# BFA_sch.net
KiCad netlist of a schematic drawn in EAGLE
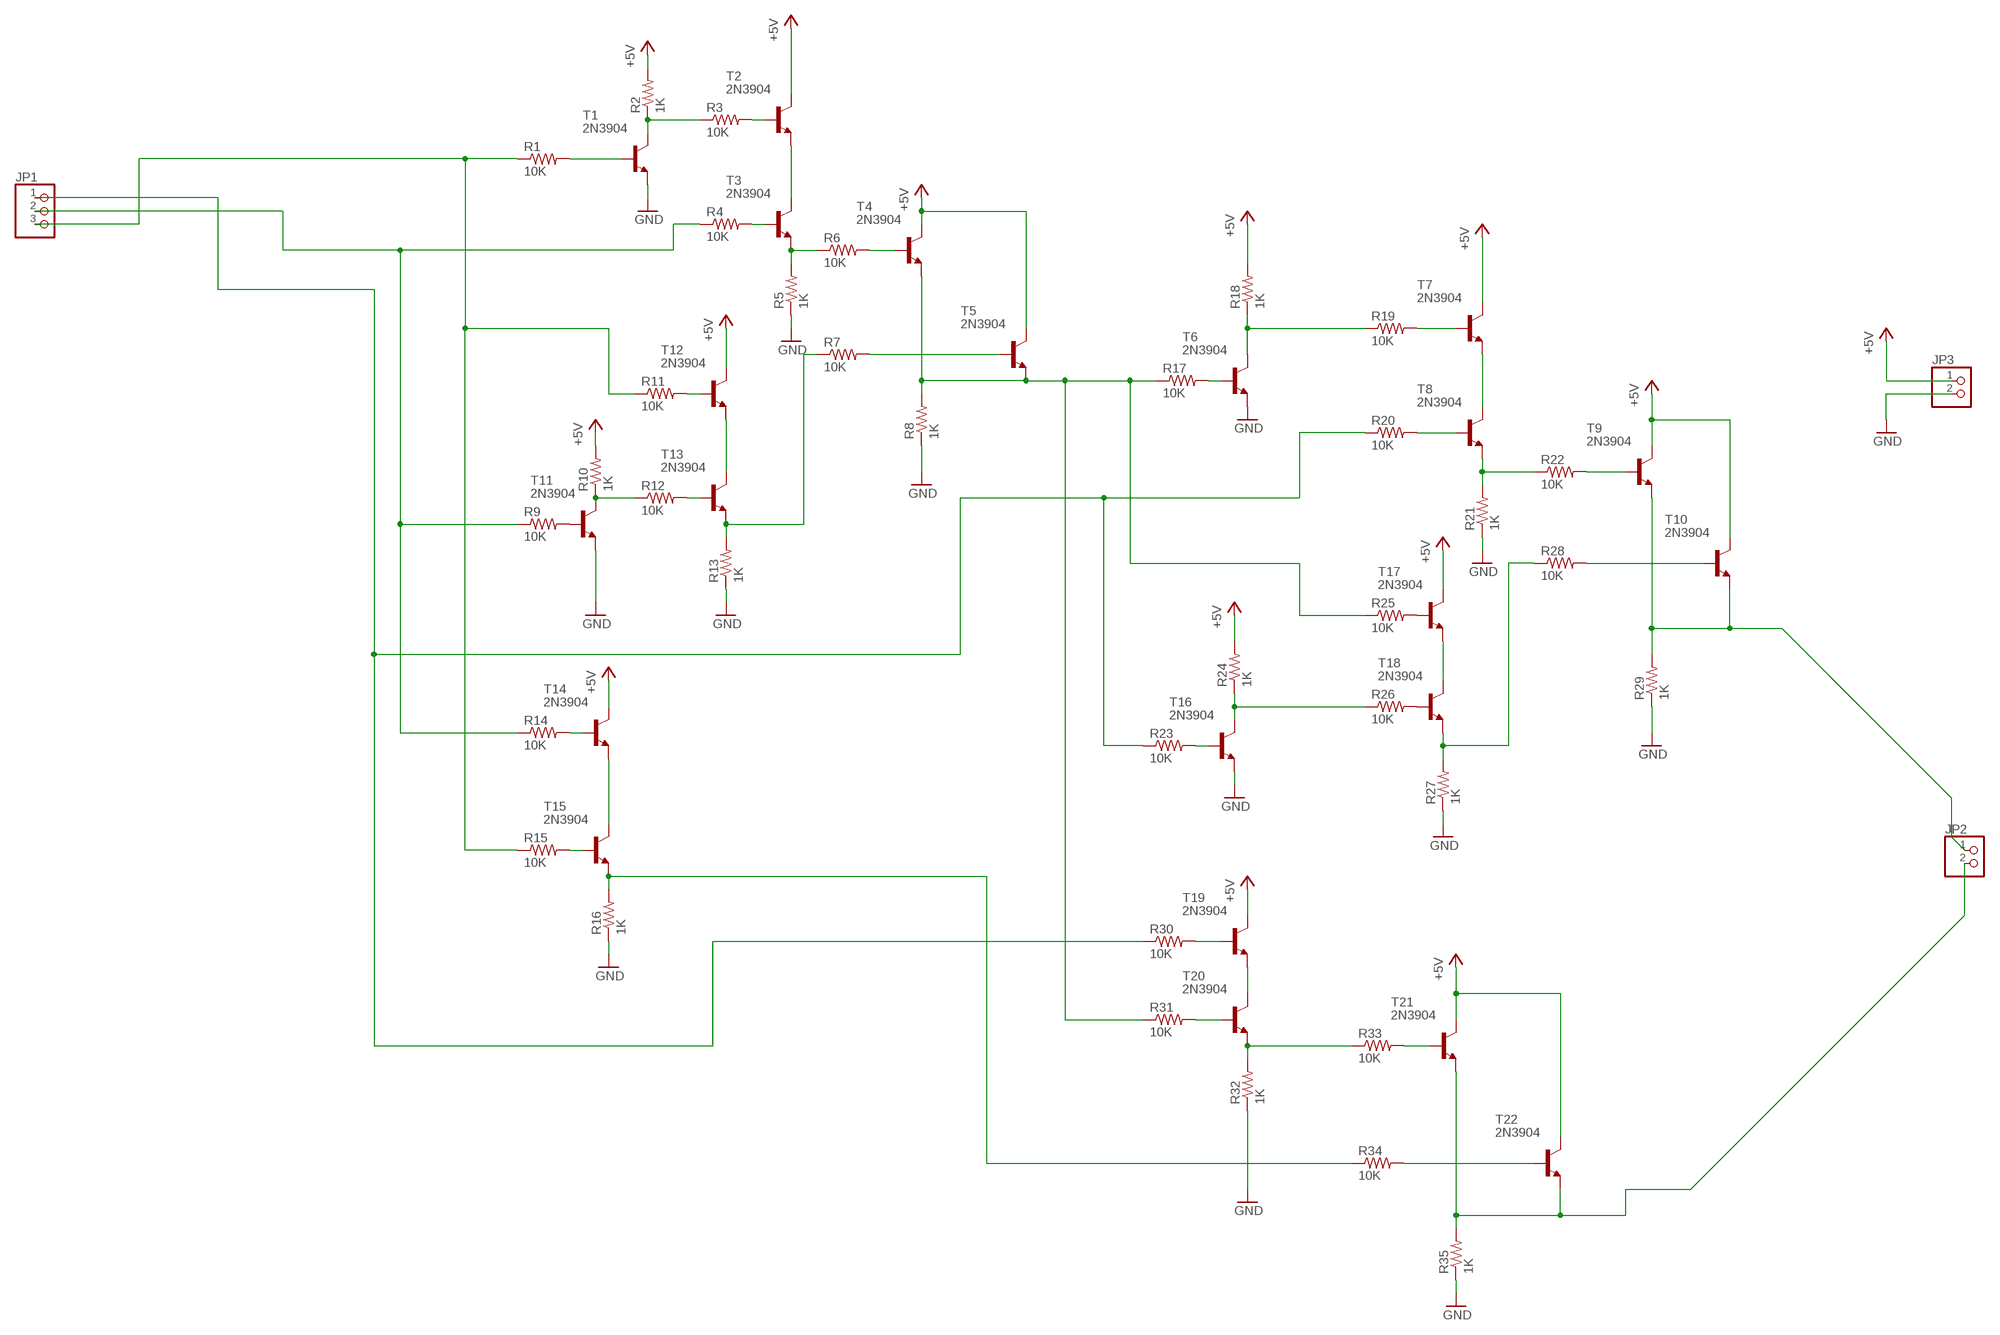
[diagram p0: schematic, sheet 1]

(export (version "E")
  (design (tool "Eeschema 10.0.6"))
  (components
    (comp (ref "JP1")
      (value "PINHD-1X3/90")
      (footprint "eagle-import:1X03_90")
      (libsource (lib "eagle-import") (part "PINHD-1X3/90"))
    )
    (comp (ref "JP2")
      (value "PINHD-1X2/90")
      (footprint "eagle-import:1X02_90")
      (libsource (lib "eagle-import") (part "PINHD-1X2/90"))
    )
    (comp (ref "JP3")
      (value "PINHD-1X2/90")
      (footprint "eagle-import:1X02_90")
      (libsource (lib "eagle-import") (part "PINHD-1X2/90"))
    )
    (comp (ref "R1")
      (value "10K")
      (footprint "eagle-import:0204_7")
      (libsource (lib "eagle-import") (part "R-US_0204/7"))
    )
    (comp (ref "R2")
      (value "1K")
      (footprint "eagle-import:0204_7")
      (libsource (lib "eagle-import") (part "R-US_0204/7"))
    )
    (comp (ref "R3")
      (value "10K")
      (footprint "eagle-import:0204_7")
      (libsource (lib "eagle-import") (part "R-US_0204/7"))
    )
    (comp (ref "R4")
      (value "10K")
      (footprint "eagle-import:0204_7")
      (libsource (lib "eagle-import") (part "R-US_0204/7"))
    )
    (comp (ref "R5")
      (value "1K")
      (footprint "eagle-import:0204_7")
      (libsource (lib "eagle-import") (part "R-US_0204/7"))
    )
    (comp (ref "R6")
      (value "10K")
      (footprint "eagle-import:0204_7")
      (libsource (lib "eagle-import") (part "R-US_0204/7"))
    )
    (comp (ref "R7")
      (value "10K")
      (footprint "eagle-import:0204_7")
      (libsource (lib "eagle-import") (part "R-US_0204/7"))
    )
    (comp (ref "R8")
      (value "1K")
      (footprint "eagle-import:0204_7")
      (libsource (lib "eagle-import") (part "R-US_0204/7"))
    )
    (comp (ref "R9")
      (value "10K")
      (footprint "eagle-import:0204_7")
      (libsource (lib "eagle-import") (part "R-US_0204/7"))
    )
    (comp (ref "R10")
      (value "1K")
      (footprint "eagle-import:0204_7")
      (libsource (lib "eagle-import") (part "R-US_0204/7"))
    )
    (comp (ref "R11")
      (value "10K")
      (footprint "eagle-import:0204_7")
      (libsource (lib "eagle-import") (part "R-US_0204/7"))
    )
    (comp (ref "R12")
      (value "10K")
      (footprint "eagle-import:0204_7")
      (libsource (lib "eagle-import") (part "R-US_0204/7"))
    )
    (comp (ref "R13")
      (value "1K")
      (footprint "eagle-import:0204_7")
      (libsource (lib "eagle-import") (part "R-US_0204/7"))
    )
    (comp (ref "R14")
      (value "10K")
      (footprint "eagle-import:0204_7")
      (libsource (lib "eagle-import") (part "R-US_0204/7"))
    )
    (comp (ref "R15")
      (value "10K")
      (footprint "eagle-import:0204_7")
      (libsource (lib "eagle-import") (part "R-US_0204/7"))
    )
    (comp (ref "R16")
      (value "1K")
      (footprint "eagle-import:0204_7")
      (libsource (lib "eagle-import") (part "R-US_0204/7"))
    )
    (comp (ref "R17")
      (value "10K")
      (footprint "eagle-import:0204_7")
      (libsource (lib "eagle-import") (part "R-US_0204/7"))
    )
    (comp (ref "R18")
      (value "1K")
      (footprint "eagle-import:0204_7")
      (libsource (lib "eagle-import") (part "R-US_0204/7"))
    )
    (comp (ref "R19")
      (value "10K")
      (footprint "eagle-import:0204_7")
      (libsource (lib "eagle-import") (part "R-US_0204/7"))
    )
    (comp (ref "R20")
      (value "10K")
      (footprint "eagle-import:0204_7")
      (libsource (lib "eagle-import") (part "R-US_0204/7"))
    )
    (comp (ref "R21")
      (value "1K")
      (footprint "eagle-import:0204_7")
      (libsource (lib "eagle-import") (part "R-US_0204/7"))
    )
    (comp (ref "R22")
      (value "10K")
      (footprint "eagle-import:0204_7")
      (libsource (lib "eagle-import") (part "R-US_0204/7"))
    )
    (comp (ref "R23")
      (value "10K")
      (footprint "eagle-import:0204_7")
      (libsource (lib "eagle-import") (part "R-US_0204/7"))
    )
    (comp (ref "R24")
      (value "1K")
      (footprint "eagle-import:0204_7")
      (libsource (lib "eagle-import") (part "R-US_0204/7"))
    )
    (comp (ref "R25")
      (value "10K")
      (footprint "eagle-import:0204_7")
      (libsource (lib "eagle-import") (part "R-US_0204/7"))
    )
    (comp (ref "R26")
      (value "10K")
      (footprint "eagle-import:0204_7")
      (libsource (lib "eagle-import") (part "R-US_0204/7"))
    )
    (comp (ref "R27")
      (value "1K")
      (footprint "eagle-import:0204_7")
      (libsource (lib "eagle-import") (part "R-US_0204/7"))
    )
    (comp (ref "R28")
      (value "10K")
      (footprint "eagle-import:0204_7")
      (libsource (lib "eagle-import") (part "R-US_0204/7"))
    )
    (comp (ref "R29")
      (value "1K")
      (footprint "eagle-import:0204_7")
      (libsource (lib "eagle-import") (part "R-US_0204/7"))
    )
    (comp (ref "R30")
      (value "10K")
      (footprint "eagle-import:0204_7")
      (libsource (lib "eagle-import") (part "R-US_0204/7"))
    )
    (comp (ref "R31")
      (value "10K")
      (footprint "eagle-import:0204_7")
      (libsource (lib "eagle-import") (part "R-US_0204/7"))
    )
    (comp (ref "R32")
      (value "1K")
      (footprint "eagle-import:0204_7")
      (libsource (lib "eagle-import") (part "R-US_0204/7"))
    )
    (comp (ref "R33")
      (value "10K")
      (footprint "eagle-import:0204_7")
      (libsource (lib "eagle-import") (part "R-US_0204/7"))
    )
    (comp (ref "R34")
      (value "10K")
      (footprint "eagle-import:0204_7")
      (libsource (lib "eagle-import") (part "R-US_0204/7"))
    )
    (comp (ref "R35")
      (value "1K")
      (footprint "eagle-import:0204_7")
      (libsource (lib "eagle-import") (part "R-US_0204/7"))
    )
    (comp (ref "T1")
      (value "2N3904")
      (footprint "eagle-import:TO92")
      (libsource (lib "eagle-import") (part "2N3904"))
    )
    (comp (ref "T2")
      (value "2N3904")
      (footprint "eagle-import:TO92")
      (libsource (lib "eagle-import") (part "2N3904"))
    )
    (comp (ref "T3")
      (value "2N3904")
      (footprint "eagle-import:TO92")
      (libsource (lib "eagle-import") (part "2N3904"))
    )
    (comp (ref "T4")
      (value "2N3904")
      (footprint "eagle-import:TO92")
      (libsource (lib "eagle-import") (part "2N3904"))
    )
    (comp (ref "T5")
      (value "2N3904")
      (footprint "eagle-import:TO92")
      (libsource (lib "eagle-import") (part "2N3904"))
    )
    (comp (ref "T6")
      (value "2N3904")
      (footprint "eagle-import:TO92")
      (libsource (lib "eagle-import") (part "2N3904"))
    )
    (comp (ref "T7")
      (value "2N3904")
      (footprint "eagle-import:TO92")
      (libsource (lib "eagle-import") (part "2N3904"))
    )
    (comp (ref "T8")
      (value "2N3904")
      (footprint "eagle-import:TO92")
      (libsource (lib "eagle-import") (part "2N3904"))
    )
    (comp (ref "T9")
      (value "2N3904")
      (footprint "eagle-import:TO92")
      (libsource (lib "eagle-import") (part "2N3904"))
    )
    (comp (ref "T10")
      (value "2N3904")
      (footprint "eagle-import:TO92")
      (libsource (lib "eagle-import") (part "2N3904"))
    )
    (comp (ref "T11")
      (value "2N3904")
      (footprint "eagle-import:TO92")
      (libsource (lib "eagle-import") (part "2N3904"))
    )
    (comp (ref "T12")
      (value "2N3904")
      (footprint "eagle-import:TO92")
      (libsource (lib "eagle-import") (part "2N3904"))
    )
    (comp (ref "T13")
      (value "2N3904")
      (footprint "eagle-import:TO92")
      (libsource (lib "eagle-import") (part "2N3904"))
    )
    (comp (ref "T14")
      (value "2N3904")
      (footprint "eagle-import:TO92")
      (libsource (lib "eagle-import") (part "2N3904"))
    )
    (comp (ref "T15")
      (value "2N3904")
      (footprint "eagle-import:TO92")
      (libsource (lib "eagle-import") (part "2N3904"))
    )
    (comp (ref "T16")
      (value "2N3904")
      (footprint "eagle-import:TO92")
      (libsource (lib "eagle-import") (part "2N3904"))
    )
    (comp (ref "T17")
      (value "2N3904")
      (footprint "eagle-import:TO92")
      (libsource (lib "eagle-import") (part "2N3904"))
    )
    (comp (ref "T18")
      (value "2N3904")
      (footprint "eagle-import:TO92")
      (libsource (lib "eagle-import") (part "2N3904"))
    )
    (comp (ref "T19")
      (value "2N3904")
      (footprint "eagle-import:TO92")
      (libsource (lib "eagle-import") (part "2N3904"))
    )
    (comp (ref "T20")
      (value "2N3904")
      (footprint "eagle-import:TO92")
      (libsource (lib "eagle-import") (part "2N3904"))
    )
    (comp (ref "T21")
      (value "2N3904")
      (footprint "eagle-import:TO92")
      (libsource (lib "eagle-import") (part "2N3904"))
    )
    (comp (ref "T22")
      (value "2N3904")
      (footprint "eagle-import:TO92")
      (libsource (lib "eagle-import") (part "2N3904"))
    )
  )
  (nets
    (net (code "1") (name "+5V") (class "Default")
      (node (ref "JP3") (pin "1") (pinfunction "1_1") (pintype "passive"))
      (node (ref "R10") (pin "2") (pinfunction "2_2") (pintype "passive"))
      (node (ref "R18") (pin "2") (pinfunction "2_2") (pintype "passive"))
      (node (ref "R2") (pin "2") (pinfunction "2_2") (pintype "passive"))
      (node (ref "R24") (pin "2") (pinfunction "2_2") (pintype "passive"))
      (node (ref "T10") (pin "1") (pinfunction "C_1") (pintype "passive"))
      (node (ref "T12") (pin "1") (pinfunction "C_1") (pintype "passive"))
      (node (ref "T14") (pin "1") (pinfunction "C_1") (pintype "passive"))
      (node (ref "T17") (pin "1") (pinfunction "C_1") (pintype "passive"))
      (node (ref "T19") (pin "1") (pinfunction "C_1") (pintype "passive"))
      (node (ref "T2") (pin "1") (pinfunction "C_1") (pintype "passive"))
      (node (ref "T21") (pin "1") (pinfunction "C_1") (pintype "passive"))
      (node (ref "T22") (pin "1") (pinfunction "C_1") (pintype "passive"))
      (node (ref "T4") (pin "1") (pinfunction "C_1") (pintype "passive"))
      (node (ref "T5") (pin "1") (pinfunction "C_1") (pintype "passive"))
      (node (ref "T7") (pin "1") (pinfunction "C_1") (pintype "passive"))
      (node (ref "T9") (pin "1") (pinfunction "C_1") (pintype "passive"))
    )
    (net (code "2") (name "GND") (class "Default")
      (node (ref "JP3") (pin "2") (pinfunction "2_2") (pintype "passive"))
      (node (ref "R13") (pin "1") (pinfunction "1_1") (pintype "passive"))
      (node (ref "R16") (pin "1") (pinfunction "1_1") (pintype "passive"))
      (node (ref "R21") (pin "1") (pinfunction "1_1") (pintype "passive"))
      (node (ref "R27") (pin "1") (pinfunction "1_1") (pintype "passive"))
      (node (ref "R29") (pin "1") (pinfunction "1_1") (pintype "passive"))
      (node (ref "R32") (pin "1") (pinfunction "1_1") (pintype "passive"))
      (node (ref "R35") (pin "1") (pinfunction "1_1") (pintype "passive"))
      (node (ref "R5") (pin "1") (pinfunction "1_1") (pintype "passive"))
      (node (ref "R8") (pin "1") (pinfunction "1_1") (pintype "passive"))
      (node (ref "T1") (pin "3") (pinfunction "E_3") (pintype "passive"))
      (node (ref "T11") (pin "3") (pinfunction "E_3") (pintype "passive"))
      (node (ref "T16") (pin "3") (pinfunction "E_3") (pintype "passive"))
      (node (ref "T6") (pin "3") (pinfunction "E_3") (pintype "passive"))
    )
    (net (code "3") (name "Net-(JP1-Pad1)") (class "Default")
      (node (ref "JP1") (pin "1") (pinfunction "1_1") (pintype "passive"))
      (node (ref "R20") (pin "1") (pinfunction "1_1") (pintype "passive"))
      (node (ref "R23") (pin "1") (pinfunction "1_1") (pintype "passive"))
      (node (ref "R30") (pin "1") (pinfunction "1_1") (pintype "passive"))
    )
    (net (code "4") (name "Net-(JP1-Pad2)") (class "Default")
      (node (ref "JP1") (pin "2") (pinfunction "2_2") (pintype "passive"))
      (node (ref "R14") (pin "1") (pinfunction "1_1") (pintype "passive"))
      (node (ref "R4") (pin "1") (pinfunction "1_1") (pintype "passive"))
      (node (ref "R9") (pin "1") (pinfunction "1_1") (pintype "passive"))
    )
    (net (code "5") (name "Net-(JP1-Pad3)") (class "Default")
      (node (ref "JP1") (pin "3") (pinfunction "3_3") (pintype "passive"))
      (node (ref "R1") (pin "1") (pinfunction "1_1") (pintype "passive"))
      (node (ref "R11") (pin "1") (pinfunction "1_1") (pintype "passive"))
      (node (ref "R15") (pin "1") (pinfunction "1_1") (pintype "passive"))
    )
    (net (code "6") (name "Net-(T1-B)") (class "Default")
      (node (ref "R1") (pin "2") (pinfunction "2_2") (pintype "passive"))
      (node (ref "T1") (pin "2") (pinfunction "B_2") (pintype "passive"))
    )
    (net (code "7") (name "Net-(T1-C)") (class "Default")
      (node (ref "R2") (pin "1") (pinfunction "1_1") (pintype "passive"))
      (node (ref "R3") (pin "1") (pinfunction "1_1") (pintype "passive"))
      (node (ref "T1") (pin "1") (pinfunction "C_1") (pintype "passive"))
    )
    (net (code "8") (name "Net-(T2-B)") (class "Default")
      (node (ref "R3") (pin "2") (pinfunction "2_2") (pintype "passive"))
      (node (ref "T2") (pin "2") (pinfunction "B_2") (pintype "passive"))
    )
    (net (code "9") (name "Net-(T2-E)") (class "Default")
      (node (ref "T2") (pin "3") (pinfunction "E_3") (pintype "passive"))
      (node (ref "T3") (pin "1") (pinfunction "C_1") (pintype "passive"))
    )
    (net (code "10") (name "Net-(T3-B)") (class "Default")
      (node (ref "R4") (pin "2") (pinfunction "2_2") (pintype "passive"))
      (node (ref "T3") (pin "2") (pinfunction "B_2") (pintype "passive"))
    )
    (net (code "11") (name "Net-(T3-E)") (class "Default")
      (node (ref "R5") (pin "2") (pinfunction "2_2") (pintype "passive"))
      (node (ref "R6") (pin "1") (pinfunction "1_1") (pintype "passive"))
      (node (ref "T3") (pin "3") (pinfunction "E_3") (pintype "passive"))
    )
    (net (code "12") (name "Net-(T4-B)") (class "Default")
      (node (ref "R6") (pin "2") (pinfunction "2_2") (pintype "passive"))
      (node (ref "T4") (pin "2") (pinfunction "B_2") (pintype "passive"))
    )
    (net (code "13") (name "Net-(T4-E)") (class "Default")
      (node (ref "R17") (pin "1") (pinfunction "1_1") (pintype "passive"))
      (node (ref "R25") (pin "1") (pinfunction "1_1") (pintype "passive"))
      (node (ref "R31") (pin "1") (pinfunction "1_1") (pintype "passive"))
      (node (ref "R8") (pin "2") (pinfunction "2_2") (pintype "passive"))
      (node (ref "T4") (pin "3") (pinfunction "E_3") (pintype "passive"))
      (node (ref "T5") (pin "3") (pinfunction "E_3") (pintype "passive"))
    )
    (net (code "14") (name "Net-(T5-B)") (class "Default")
      (node (ref "R7") (pin "2") (pinfunction "2_2") (pintype "passive"))
      (node (ref "T5") (pin "2") (pinfunction "B_2") (pintype "passive"))
    )
    (net (code "15") (name "Net-(T6-B)") (class "Default")
      (node (ref "R17") (pin "2") (pinfunction "2_2") (pintype "passive"))
      (node (ref "T6") (pin "2") (pinfunction "B_2") (pintype "passive"))
    )
    (net (code "16") (name "Net-(T6-C)") (class "Default")
      (node (ref "R18") (pin "1") (pinfunction "1_1") (pintype "passive"))
      (node (ref "R19") (pin "1") (pinfunction "1_1") (pintype "passive"))
      (node (ref "T6") (pin "1") (pinfunction "C_1") (pintype "passive"))
    )
    (net (code "17") (name "Net-(T7-B)") (class "Default")
      (node (ref "R19") (pin "2") (pinfunction "2_2") (pintype "passive"))
      (node (ref "T7") (pin "2") (pinfunction "B_2") (pintype "passive"))
    )
    (net (code "18") (name "Net-(T7-E)") (class "Default")
      (node (ref "T7") (pin "3") (pinfunction "E_3") (pintype "passive"))
      (node (ref "T8") (pin "1") (pinfunction "C_1") (pintype "passive"))
    )
    (net (code "19") (name "Net-(T8-B)") (class "Default")
      (node (ref "R20") (pin "2") (pinfunction "2_2") (pintype "passive"))
      (node (ref "T8") (pin "2") (pinfunction "B_2") (pintype "passive"))
    )
    (net (code "20") (name "Net-(T8-E)") (class "Default")
      (node (ref "R21") (pin "2") (pinfunction "2_2") (pintype "passive"))
      (node (ref "R22") (pin "1") (pinfunction "1_1") (pintype "passive"))
      (node (ref "T8") (pin "3") (pinfunction "E_3") (pintype "passive"))
    )
    (net (code "21") (name "Net-(T9-B)") (class "Default")
      (node (ref "R22") (pin "2") (pinfunction "2_2") (pintype "passive"))
      (node (ref "T9") (pin "2") (pinfunction "B_2") (pintype "passive"))
    )
    (net (code "22") (name "Net-(T10-B)") (class "Default")
      (node (ref "R28") (pin "2") (pinfunction "2_2") (pintype "passive"))
      (node (ref "T10") (pin "2") (pinfunction "B_2") (pintype "passive"))
    )
    (net (code "23") (name "Net-(T10-E)") (class "Default")
      (node (ref "JP2") (pin "1") (pinfunction "1_1") (pintype "passive"))
      (node (ref "R29") (pin "2") (pinfunction "2_2") (pintype "passive"))
      (node (ref "T10") (pin "3") (pinfunction "E_3") (pintype "passive"))
      (node (ref "T9") (pin "3") (pinfunction "E_3") (pintype "passive"))
    )
    (net (code "24") (name "Net-(T11-B)") (class "Default")
      (node (ref "R9") (pin "2") (pinfunction "2_2") (pintype "passive"))
      (node (ref "T11") (pin "2") (pinfunction "B_2") (pintype "passive"))
    )
    (net (code "25") (name "Net-(T11-C)") (class "Default")
      (node (ref "R10") (pin "1") (pinfunction "1_1") (pintype "passive"))
      (node (ref "R12") (pin "1") (pinfunction "1_1") (pintype "passive"))
      (node (ref "T11") (pin "1") (pinfunction "C_1") (pintype "passive"))
    )
    (net (code "26") (name "Net-(T12-B)") (class "Default")
      (node (ref "R11") (pin "2") (pinfunction "2_2") (pintype "passive"))
      (node (ref "T12") (pin "2") (pinfunction "B_2") (pintype "passive"))
    )
    (net (code "27") (name "Net-(T12-E)") (class "Default")
      (node (ref "T12") (pin "3") (pinfunction "E_3") (pintype "passive"))
      (node (ref "T13") (pin "1") (pinfunction "C_1") (pintype "passive"))
    )
    (net (code "28") (name "Net-(T13-B)") (class "Default")
      (node (ref "R12") (pin "2") (pinfunction "2_2") (pintype "passive"))
      (node (ref "T13") (pin "2") (pinfunction "B_2") (pintype "passive"))
    )
    (net (code "29") (name "Net-(T13-E)") (class "Default")
      (node (ref "R13") (pin "2") (pinfunction "2_2") (pintype "passive"))
      (node (ref "R7") (pin "1") (pinfunction "1_1") (pintype "passive"))
      (node (ref "T13") (pin "3") (pinfunction "E_3") (pintype "passive"))
    )
    (net (code "30") (name "Net-(T14-B)") (class "Default")
      (node (ref "R14") (pin "2") (pinfunction "2_2") (pintype "passive"))
      (node (ref "T14") (pin "2") (pinfunction "B_2") (pintype "passive"))
    )
    (net (code "31") (name "Net-(T14-E)") (class "Default")
      (node (ref "T14") (pin "3") (pinfunction "E_3") (pintype "passive"))
      (node (ref "T15") (pin "1") (pinfunction "C_1") (pintype "passive"))
    )
    (net (code "32") (name "Net-(T15-B)") (class "Default")
      (node (ref "R15") (pin "2") (pinfunction "2_2") (pintype "passive"))
      (node (ref "T15") (pin "2") (pinfunction "B_2") (pintype "passive"))
    )
    (net (code "33") (name "Net-(T15-E)") (class "Default")
      (node (ref "R16") (pin "2") (pinfunction "2_2") (pintype "passive"))
      (node (ref "R34") (pin "1") (pinfunction "1_1") (pintype "passive"))
      (node (ref "T15") (pin "3") (pinfunction "E_3") (pintype "passive"))
    )
    (net (code "34") (name "Net-(T16-B)") (class "Default")
      (node (ref "R23") (pin "2") (pinfunction "2_2") (pintype "passive"))
      (node (ref "T16") (pin "2") (pinfunction "B_2") (pintype "passive"))
    )
    (net (code "35") (name "Net-(T16-C)") (class "Default")
      (node (ref "R24") (pin "1") (pinfunction "1_1") (pintype "passive"))
      (node (ref "R26") (pin "1") (pinfunction "1_1") (pintype "passive"))
      (node (ref "T16") (pin "1") (pinfunction "C_1") (pintype "passive"))
    )
    (net (code "36") (name "Net-(T17-B)") (class "Default")
      (node (ref "R25") (pin "2") (pinfunction "2_2") (pintype "passive"))
      (node (ref "T17") (pin "2") (pinfunction "B_2") (pintype "passive"))
    )
    (net (code "37") (name "Net-(T17-E)") (class "Default")
      (node (ref "T17") (pin "3") (pinfunction "E_3") (pintype "passive"))
      (node (ref "T18") (pin "1") (pinfunction "C_1") (pintype "passive"))
    )
    (net (code "38") (name "Net-(T18-B)") (class "Default")
      (node (ref "R26") (pin "2") (pinfunction "2_2") (pintype "passive"))
      (node (ref "T18") (pin "2") (pinfunction "B_2") (pintype "passive"))
    )
    (net (code "39") (name "Net-(T18-E)") (class "Default")
      (node (ref "R27") (pin "2") (pinfunction "2_2") (pintype "passive"))
      (node (ref "R28") (pin "1") (pinfunction "1_1") (pintype "passive"))
      (node (ref "T18") (pin "3") (pinfunction "E_3") (pintype "passive"))
    )
    (net (code "40") (name "Net-(T19-B)") (class "Default")
      (node (ref "R30") (pin "2") (pinfunction "2_2") (pintype "passive"))
      (node (ref "T19") (pin "2") (pinfunction "B_2") (pintype "passive"))
    )
    (net (code "41") (name "Net-(T19-E)") (class "Default")
      (node (ref "T19") (pin "3") (pinfunction "E_3") (pintype "passive"))
      (node (ref "T20") (pin "1") (pinfunction "C_1") (pintype "passive"))
    )
    (net (code "42") (name "Net-(T20-B)") (class "Default")
      (node (ref "R31") (pin "2") (pinfunction "2_2") (pintype "passive"))
      (node (ref "T20") (pin "2") (pinfunction "B_2") (pintype "passive"))
    )
    (net (code "43") (name "Net-(T20-E)") (class "Default")
      (node (ref "R32") (pin "2") (pinfunction "2_2") (pintype "passive"))
      (node (ref "R33") (pin "1") (pinfunction "1_1") (pintype "passive"))
      (node (ref "T20") (pin "3") (pinfunction "E_3") (pintype "passive"))
    )
    (net (code "44") (name "Net-(T21-B)") (class "Default")
      (node (ref "R33") (pin "2") (pinfunction "2_2") (pintype "passive"))
      (node (ref "T21") (pin "2") (pinfunction "B_2") (pintype "passive"))
    )
    (net (code "45") (name "Net-(T21-E)") (class "Default")
      (node (ref "JP2") (pin "2") (pinfunction "2_2") (pintype "passive"))
      (node (ref "R35") (pin "2") (pinfunction "2_2") (pintype "passive"))
      (node (ref "T21") (pin "3") (pinfunction "E_3") (pintype "passive"))
      (node (ref "T22") (pin "3") (pinfunction "E_3") (pintype "passive"))
    )
    (net (code "46") (name "Net-(T22-B)") (class "Default")
      (node (ref "R34") (pin "2") (pinfunction "2_2") (pintype "passive"))
      (node (ref "T22") (pin "2") (pinfunction "B_2") (pintype "passive"))
    )
  )
)
